# breakout.net
KiCad netlist of a schematic drawn in EAGLE
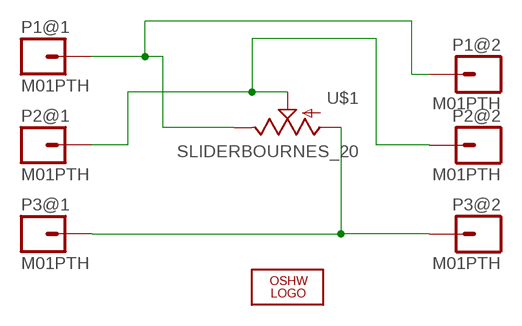
[diagram p0: schematic, sheet 1]

(export (version "E")
  (design (tool "Eeschema 10.0.6"))
  (components
    (comp (ref "LOGO1")
      (value "OSHW_LOGO_FILLX0100-NT")
      (footprint "eagle-import:OSHW_FILLX100_NOTEXT")
      (libsource (lib "eagle-import") (part "OSHW_LOGO_FILLX0100-NT"))
    )
    (comp (ref "P1@1")
      (value "M01PTH")
      (footprint "eagle-import:1X01")
      (libsource (lib "eagle-import") (part "M01PTH"))
    )
    (comp (ref "P1@2")
      (value "M01PTH")
      (footprint "eagle-import:1X01")
      (libsource (lib "eagle-import") (part "M01PTH"))
    )
    (comp (ref "P2@1")
      (value "M01PTH")
      (footprint "eagle-import:1X01")
      (libsource (lib "eagle-import") (part "M01PTH"))
    )
    (comp (ref "P2@2")
      (value "M01PTH")
      (footprint "eagle-import:1X01")
      (libsource (lib "eagle-import") (part "M01PTH"))
    )
    (comp (ref "P3@1")
      (value "M01PTH")
      (footprint "eagle-import:1X01")
      (libsource (lib "eagle-import") (part "M01PTH"))
    )
    (comp (ref "P3@2")
      (value "M01PTH")
      (footprint "eagle-import:1X01")
      (libsource (lib "eagle-import") (part "M01PTH"))
    )
    (comp (ref "U$1")
      (value "SLIDERBOURNES_20")
      (footprint "eagle-import:BOURNS_20")
      (libsource (lib "eagle-import") (part "SLIDERBOURNES_20"))
    )
  )
  (nets
    (net (code "1") (name "Net-(U$1-A)") (class "Default")
      (node (ref "P3@1") (pin "1") (pinfunction "1_1") (pintype "passive"))
      (node (ref "P3@2") (pin "1") (pinfunction "1_1") (pintype "passive"))
      (node (ref "U$1") (pin "P$3") (pinfunction "A_P$3") (pintype "passive"))
    )
    (net (code "2") (name "Net-(U$1-E)") (class "Default")
      (node (ref "P1@1") (pin "1") (pinfunction "1_1") (pintype "passive"))
      (node (ref "P1@2") (pin "1") (pinfunction "1_1") (pintype "passive"))
      (node (ref "U$1") (pin "P$1") (pinfunction "E_P$1") (pintype "passive"))
    )
    (net (code "3") (name "Net-(U$1-S)") (class "Default")
      (node (ref "P2@1") (pin "1") (pinfunction "1_1") (pintype "passive"))
      (node (ref "P2@2") (pin "1") (pinfunction "1_1") (pintype "passive"))
      (node (ref "U$1") (pin "P$2") (pinfunction "S_P$2") (pintype "passive"))
    )
  )
)
